# PE4312_V03_R00.net
KiCad netlist of a schematic drawn in Altium Designer
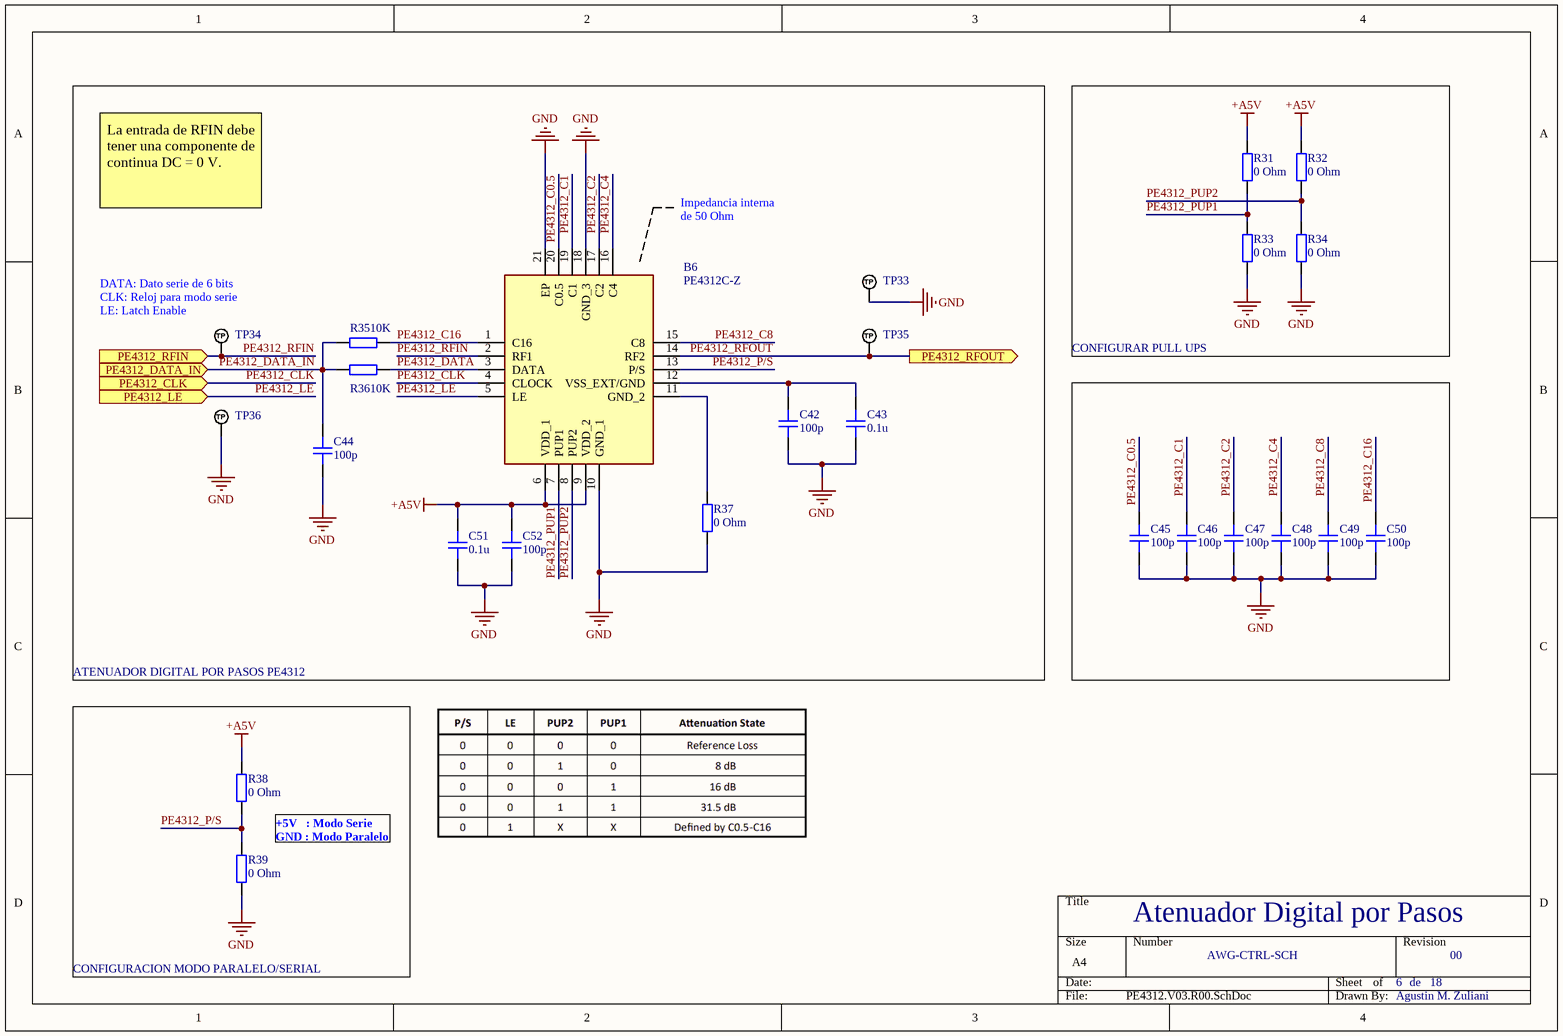
[diagram p0: PE4312.V03.R00.SchDoc]

(export (version "E")
  (design (tool "Eeschema 10.0.6"))
  (components
    (comp (ref "B6")
      (value "PE4312C-Z")
      (footprint "QFN50P400X400X90-21N-D")
      (description "RF ATTENUATOR 31.5DB 50OHM 20QFN")
      (fields (field (name "MOUSER PART NUMBER") "81-PE4312C-Z"))
      (libsource (lib "PE4312C-Z") (part "PE4312C-Z"))
    )
    (comp (ref "C42")
      (value "100p")
      (footprint "CAP_0805")
      (description "Capacitor SMD 0805")
      (libsource (lib "Schematic-Lib-PhilsLab") (part "CAP_0805"))
    )
    (comp (ref "C43")
      (value "0.1u")
      (footprint "CAP_0805")
      (description "Capacitor SMD 0805")
      (libsource (lib "Schematic-Lib-PhilsLab") (part "CAP_0805"))
    )
    (comp (ref "C44")
      (value "100p")
      (footprint "CAP_0805")
      (description "Capacitor SMD 0805")
      (libsource (lib "Schematic-Lib-PhilsLab") (part "CAP_0805"))
    )
    (comp (ref "C45")
      (value "100p")
      (footprint "CAP_0805")
      (description "Capacitor SMD 0805")
      (libsource (lib "Schematic-Lib-PhilsLab") (part "CAP_0805"))
    )
    (comp (ref "C46")
      (value "100p")
      (footprint "CAP_0805")
      (description "Capacitor SMD 0805")
      (libsource (lib "Schematic-Lib-PhilsLab") (part "CAP_0805"))
    )
    (comp (ref "C47")
      (value "100p")
      (footprint "CAP_0805")
      (description "Capacitor SMD 0805")
      (libsource (lib "Schematic-Lib-PhilsLab") (part "CAP_0805"))
    )
    (comp (ref "C48")
      (value "100p")
      (footprint "CAP_0805")
      (description "Capacitor SMD 0805")
      (libsource (lib "Schematic-Lib-PhilsLab") (part "CAP_0805"))
    )
    (comp (ref "C49")
      (value "100p")
      (footprint "CAP_0805")
      (description "Capacitor SMD 0805")
      (libsource (lib "Schematic-Lib-PhilsLab") (part "CAP_0805"))
    )
    (comp (ref "C50")
      (value "100p")
      (footprint "CAP_0805")
      (description "Capacitor SMD 0805")
      (libsource (lib "Schematic-Lib-PhilsLab") (part "CAP_0805"))
    )
    (comp (ref "C51")
      (value "0.1u")
      (footprint "CAP_0805")
      (description "Capacitor SMD 0805")
      (libsource (lib "Schematic-Lib-PhilsLab") (part "CAP_0805"))
    )
    (comp (ref "C52")
      (value "100p")
      (footprint "CAP_0805")
      (description "Capacitor SMD 0805")
      (libsource (lib "Schematic-Lib-PhilsLab") (part "CAP_0805"))
    )
    (comp (ref "R31")
      (value "0 Ohm")
      (footprint "RES_0805")
      (description "Resistor SMD 0805")
      (libsource (lib "Schematic-Lib-PhilsLab") (part "RES_0805"))
    )
    (comp (ref "R32")
      (value "0 Ohm")
      (footprint "RES_0805")
      (description "Resistor SMD 0805")
      (libsource (lib "Schematic-Lib-PhilsLab") (part "RES_0805"))
    )
    (comp (ref "R33")
      (value "0 Ohm")
      (footprint "RES_0805")
      (description "Resistor SMD 0805")
      (libsource (lib "Schematic-Lib-PhilsLab") (part "RES_0805"))
    )
    (comp (ref "R34")
      (value "0 Ohm")
      (footprint "RES_0805")
      (description "Resistor SMD 0805")
      (libsource (lib "Schematic-Lib-PhilsLab") (part "RES_0805"))
    )
    (comp (ref "R35")
      (value "10K")
      (footprint "RES_0805")
      (description "Resistor SMD 0805")
      (libsource (lib "Schematic-Lib-PhilsLab") (part "RES_0805"))
    )
    (comp (ref "R36")
      (value "10K")
      (footprint "RES_0805")
      (description "Resistor SMD 0805")
      (libsource (lib "Schematic-Lib-PhilsLab") (part "RES_0805"))
    )
    (comp (ref "R37")
      (value "0 Ohm")
      (footprint "RES_0805")
      (description "Resistor SMD 0805")
      (libsource (lib "Schematic-Lib-PhilsLab") (part "RES_0805"))
    )
    (comp (ref "R38")
      (value "0 Ohm")
      (footprint "RES_0805")
      (description "Resistor SMD 0805")
      (libsource (lib "Schematic-Lib-PhilsLab") (part "RES_0805"))
    )
    (comp (ref "R39")
      (value "0 Ohm")
      (footprint "RES_0805")
      (description "Resistor SMD 0805")
      (libsource (lib "Schematic-Lib-PhilsLab") (part "RES_0805"))
    )
    (comp (ref "TP33")
      (value "TP_NOBOM")
      (footprint "PAD_RND_1MM")
      (description "Test Point Round 1mm (NO BOM)")
      (libsource (lib "Schematic-Lib-PhilsLab") (part "TEST_POINT_RND_1MM"))
    )
    (comp (ref "TP34")
      (value "TP_NOBOM")
      (footprint "PAD_RND_1MM")
      (description "Test Point Round 1mm (NO BOM)")
      (libsource (lib "Schematic-Lib-PhilsLab") (part "TEST_POINT_RND_1MM"))
    )
    (comp (ref "TP35")
      (value "TP_NOBOM")
      (footprint "PAD_RND_1MM")
      (description "Test Point Round 1mm (NO BOM)")
      (libsource (lib "Schematic-Lib-PhilsLab") (part "TEST_POINT_RND_1MM"))
    )
    (comp (ref "TP36")
      (value "TP_NOBOM")
      (footprint "PAD_RND_1MM")
      (description "Test Point Round 1mm (NO BOM)")
      (libsource (lib "Schematic-Lib-PhilsLab") (part "TEST_POINT_RND_1MM"))
    )
  )
  (nets
    (net (code "1") (name "+A5V") (class "Default")
      (node (ref "B6") (pin "6") (pinfunction "VDD_1_6") (pintype "passive"))
      (node (ref "B6") (pin "9") (pinfunction "VDD_2_9") (pintype "passive"))
      (node (ref "C51") (pin "2") (pinfunction "2_2") (pintype "passive"))
      (node (ref "C52") (pin "2") (pinfunction "2_2") (pintype "passive"))
      (node (ref "R31") (pin "2") (pinfunction "2_2") (pintype "passive"))
      (node (ref "R32") (pin "2") (pinfunction "2_2") (pintype "passive"))
      (node (ref "R38") (pin "2") (pinfunction "2_2") (pintype "passive"))
    )
    (net (code "2") (name "/PE4312_C0.5") (class "Default")
      (node (ref "B6") (pin "20") (pinfunction "C0.5_20") (pintype "passive"))
      (node (ref "C45") (pin "2") (pinfunction "2_2") (pintype "passive"))
    )
    (net (code "3") (name "/PE4312_C1") (class "Default")
      (node (ref "B6") (pin "19") (pinfunction "C1_19") (pintype "passive"))
      (node (ref "C46") (pin "2") (pinfunction "2_2") (pintype "passive"))
    )
    (net (code "4") (name "/PE4312_C2") (class "Default")
      (node (ref "B6") (pin "17") (pinfunction "C2_17") (pintype "passive"))
      (node (ref "C47") (pin "2") (pinfunction "2_2") (pintype "passive"))
    )
    (net (code "5") (name "/PE4312_C4") (class "Default")
      (node (ref "B6") (pin "16") (pinfunction "C4_16") (pintype "passive"))
      (node (ref "C48") (pin "2") (pinfunction "2_2") (pintype "passive"))
    )
    (net (code "6") (name "/PE4312_C8") (class "Default")
      (node (ref "B6") (pin "15") (pinfunction "C8_15") (pintype "passive"))
      (node (ref "C49") (pin "2") (pinfunction "2_2") (pintype "passive"))
    )
    (net (code "7") (name "/PE4312_C16") (class "Default")
      (node (ref "B6") (pin "1") (pinfunction "C16_1") (pintype "passive"))
      (node (ref "C50") (pin "2") (pinfunction "2_2") (pintype "passive"))
      (node (ref "R35") (pin "2") (pinfunction "2_2") (pintype "passive"))
    )
    (net (code "8") (name "/PE4312_CLK") (class "Default")
      (node (ref "B6") (pin "4") (pinfunction "CLOCK_4") (pintype "passive"))
    )
    (net (code "9") (name "/PE4312_DATA") (class "Default")
      (node (ref "B6") (pin "3") (pinfunction "DATA_3") (pintype "passive"))
      (node (ref "R36") (pin "2") (pinfunction "2_2") (pintype "passive"))
    )
    (net (code "10") (name "/PE4312_DATA_IN") (class "Default")
      (node (ref "C44") (pin "2") (pinfunction "2_2") (pintype "passive"))
      (node (ref "R35") (pin "1") (pinfunction "1_1") (pintype "passive"))
      (node (ref "R36") (pin "1") (pinfunction "1_1") (pintype "passive"))
    )
    (net (code "11") (name "/PE4312_LE") (class "Default")
      (node (ref "B6") (pin "5") (pinfunction "LE_5") (pintype "passive"))
    )
    (net (code "12") (name "/PE4312_PUP1") (class "Default")
      (node (ref "B6") (pin "7") (pinfunction "PUP1_7") (pintype "passive"))
      (node (ref "R31") (pin "1") (pinfunction "1_1") (pintype "passive"))
      (node (ref "R33") (pin "2") (pinfunction "2_2") (pintype "passive"))
    )
    (net (code "13") (name "/PE4312_PUP2") (class "Default")
      (node (ref "B6") (pin "8") (pinfunction "PUP2_8") (pintype "passive"))
      (node (ref "R32") (pin "1") (pinfunction "1_1") (pintype "passive"))
      (node (ref "R34") (pin "2") (pinfunction "2_2") (pintype "passive"))
    )
    (net (code "14") (name "/PE4312_P{slash}S") (class "Default")
      (node (ref "B6") (pin "13") (pinfunction "P/S_13") (pintype "passive"))
      (node (ref "R38") (pin "1") (pinfunction "1_1") (pintype "passive"))
      (node (ref "R39") (pin "2") (pinfunction "2_2") (pintype "passive"))
    )
    (net (code "15") (name "/PE4312_RFIN") (class "Default")
      (node (ref "B6") (pin "2") (pinfunction "RF1_2") (pintype "passive"))
      (node (ref "TP34") (pin "1") (pinfunction "TP_1") (pintype "passive"))
    )
    (net (code "16") (name "/PE4312_RFOUT") (class "Default")
      (node (ref "B6") (pin "14") (pinfunction "RF2_14") (pintype "passive"))
      (node (ref "TP35") (pin "1") (pinfunction "TP_1") (pintype "passive"))
    )
    (net (code "17") (name "GND") (class "Default")
      (node (ref "B6") (pin "10") (pinfunction "GND_1_10") (pintype "passive"))
      (node (ref "B6") (pin "18") (pinfunction "GND_3_18") (pintype "passive"))
      (node (ref "B6") (pin "21") (pinfunction "EP_21") (pintype "passive"))
      (node (ref "C42") (pin "1") (pinfunction "1_1") (pintype "passive"))
      (node (ref "C43") (pin "1") (pinfunction "1_1") (pintype "passive"))
      (node (ref "C44") (pin "1") (pinfunction "1_1") (pintype "passive"))
      (node (ref "C45") (pin "1") (pinfunction "1_1") (pintype "passive"))
      (node (ref "C46") (pin "1") (pinfunction "1_1") (pintype "passive"))
      (node (ref "C47") (pin "1") (pinfunction "1_1") (pintype "passive"))
      (node (ref "C48") (pin "1") (pinfunction "1_1") (pintype "passive"))
      (node (ref "C49") (pin "1") (pinfunction "1_1") (pintype "passive"))
      (node (ref "C50") (pin "1") (pinfunction "1_1") (pintype "passive"))
      (node (ref "C51") (pin "1") (pinfunction "1_1") (pintype "passive"))
      (node (ref "C52") (pin "1") (pinfunction "1_1") (pintype "passive"))
      (node (ref "R33") (pin "1") (pinfunction "1_1") (pintype "passive"))
      (node (ref "R34") (pin "1") (pinfunction "1_1") (pintype "passive"))
      (node (ref "R37") (pin "1") (pinfunction "1_1") (pintype "passive"))
      (node (ref "R39") (pin "1") (pinfunction "1_1") (pintype "passive"))
      (node (ref "TP33") (pin "1") (pinfunction "TP_1") (pintype "passive"))
      (node (ref "TP36") (pin "1") (pinfunction "TP_1") (pintype "passive"))
    )
    (net (code "18") (name "Net-(B6-GND_2)") (class "Default")
      (node (ref "B6") (pin "11") (pinfunction "GND_2_11") (pintype "passive"))
      (node (ref "R37") (pin "2") (pinfunction "2_2") (pintype "passive"))
    )
    (net (code "19") (name "Net-(B6-VSS_EXT{slash}GND)") (class "Default")
      (node (ref "B6") (pin "12") (pinfunction "VSS_EXT/GND_12") (pintype "passive"))
      (node (ref "C42") (pin "2") (pinfunction "2_2") (pintype "passive"))
      (node (ref "C43") (pin "2") (pinfunction "2_2") (pintype "passive"))
    )
  )
)
